# BluetoothAdapter3_0.net
KiCad netlist of a schematic drawn in Altium Designer
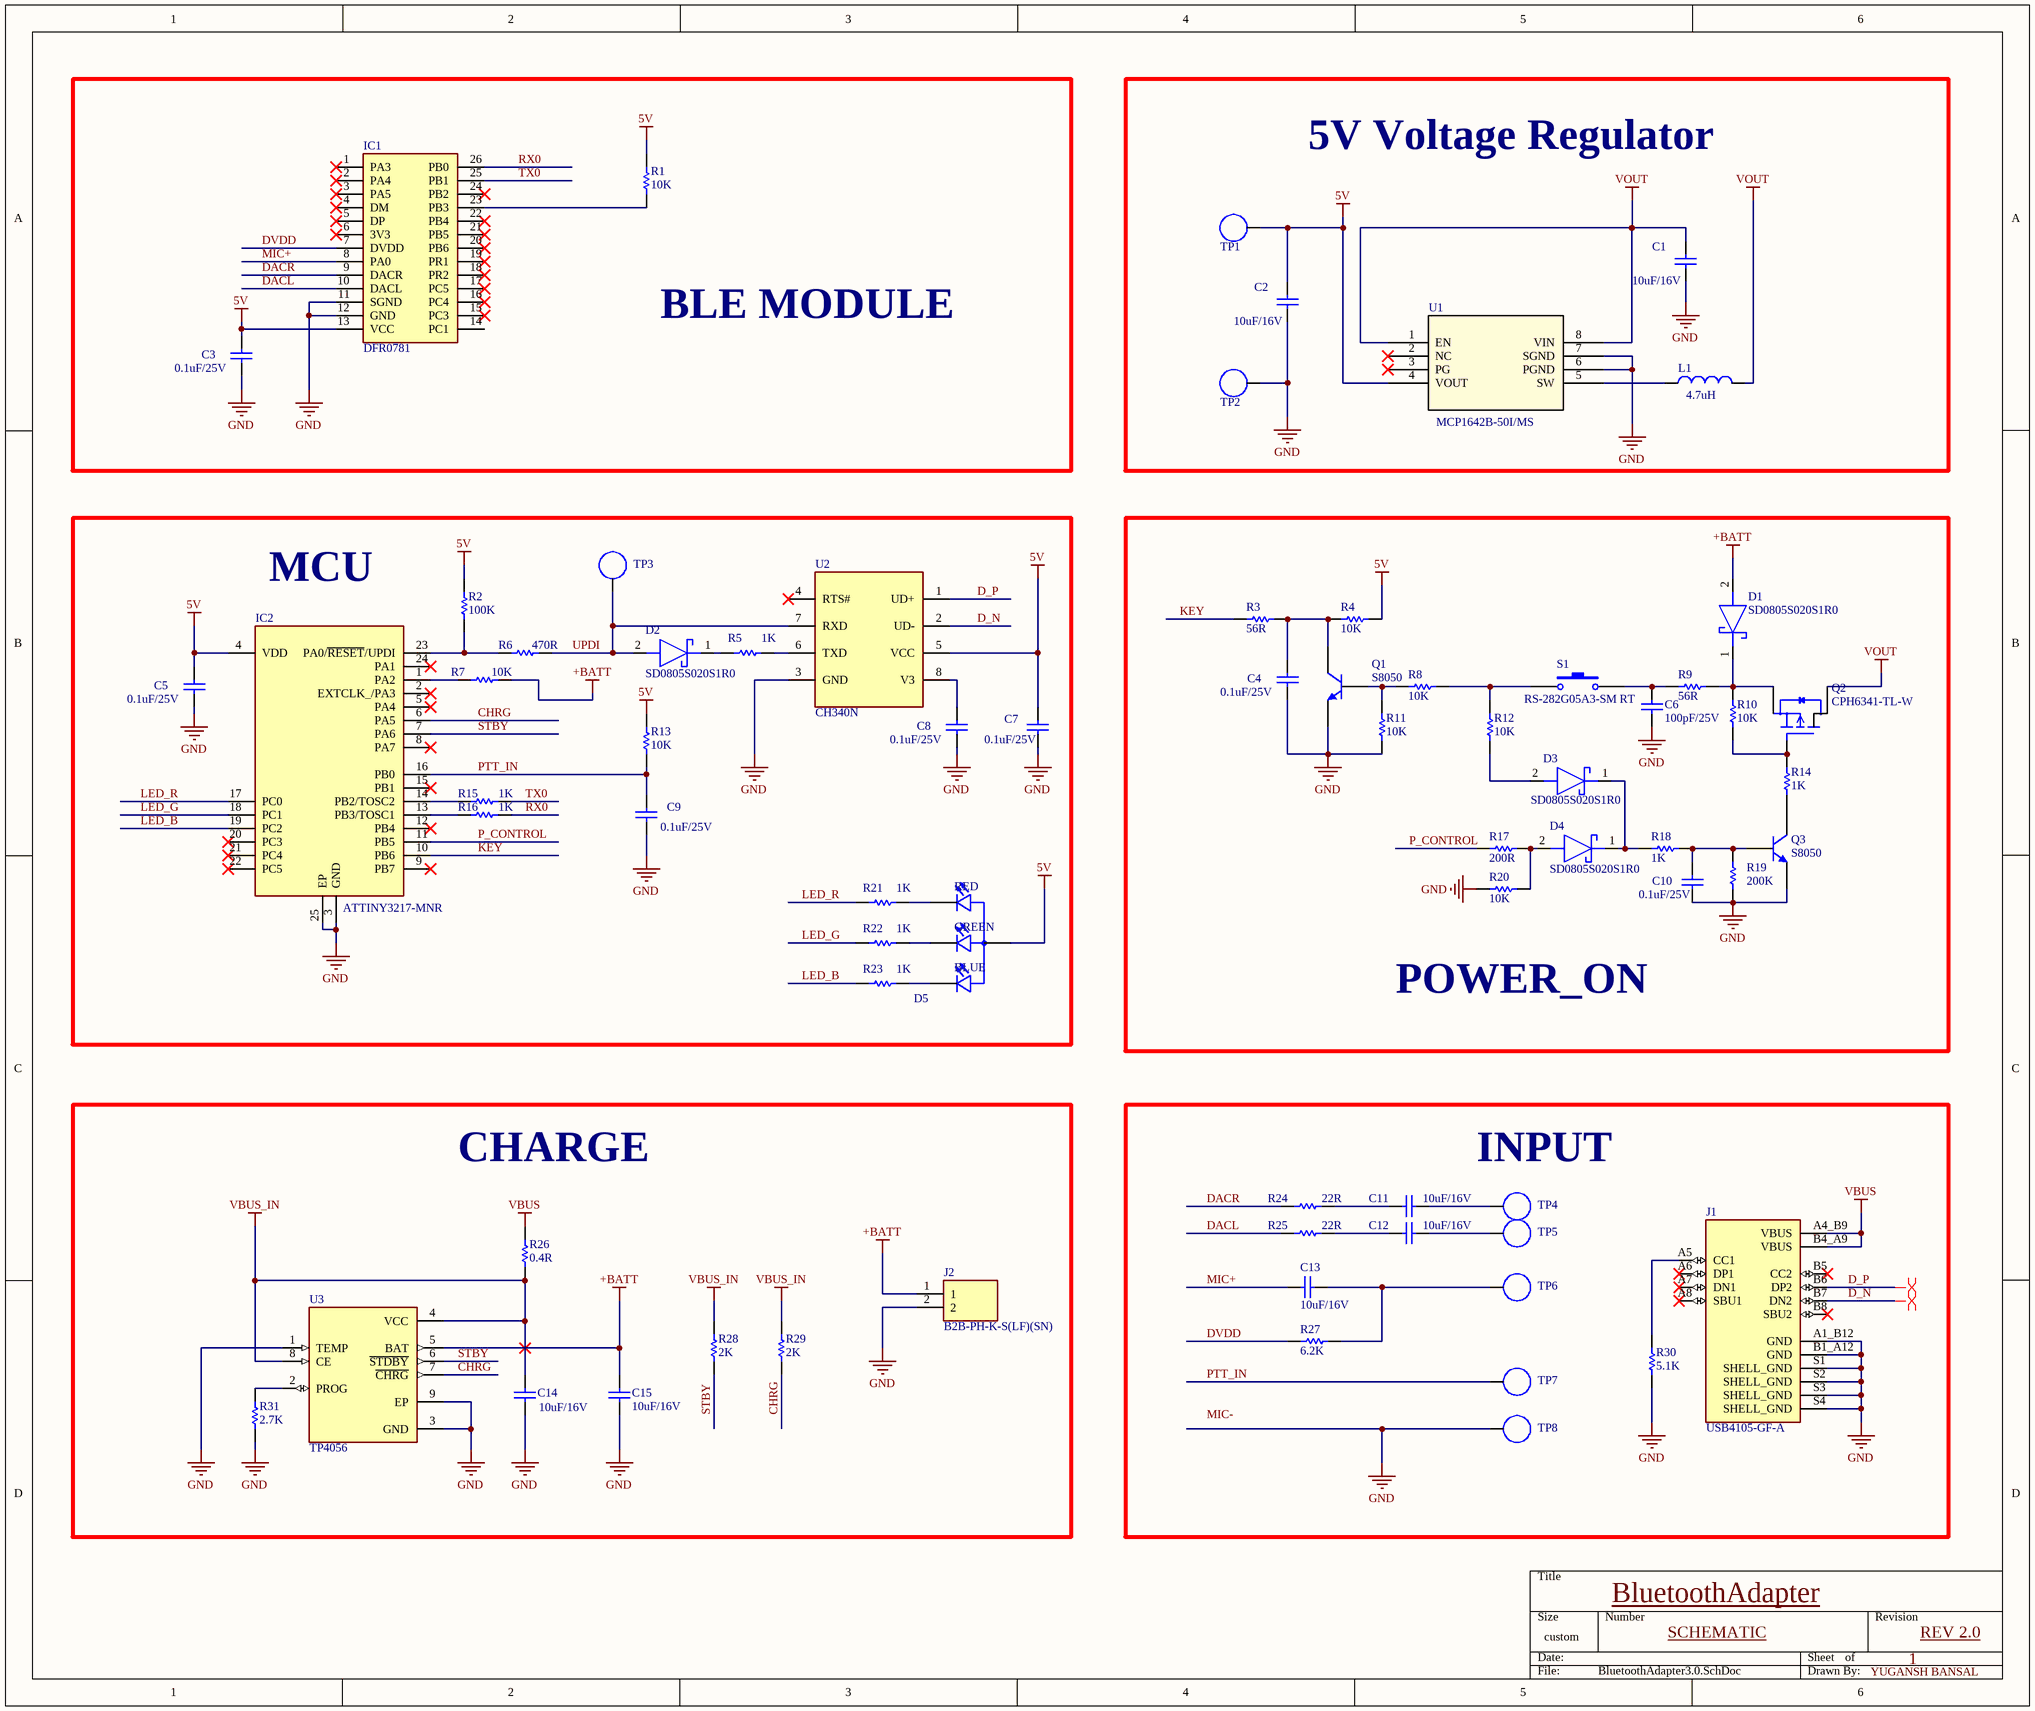
[diagram p0: BluetoothAdapter3.0.SchDoc]

(export (version "E")
  (design (tool "Eeschema 10.0.6"))
  (components
    (comp (ref "C1")
      (value "10uF/16V")
      (footprint "BluetoothAdapter:C0603S")
      (description "10 µF ±20% 16V Ceramic Capacitor X5R 0603 (1608 Metric)")
      (fields
        (field (name "MANUFACTURER") "Murata Electronics")
        (field (name "DIGI-KEY PART NUMBER") "490-10729-6-ND")
      )
      (libsource (lib "myLib") (part "Cap"))
    )
    (comp (ref "C2")
      (value "10uF/16V")
      (footprint "BluetoothAdapter:C0603S")
      (description "10 µF ±20% 16V Ceramic Capacitor X5R 0603 (1608 Metric)")
      (fields
        (field (name "MANUFACTURER") "Murata Electronics")
        (field (name "DIGI-KEY PART NUMBER") "490-10729-6-ND")
      )
      (libsource (lib "myLib") (part "Cap"))
    )
    (comp (ref "C3")
      (value "0.1uF/25V")
      (footprint "BluetoothAdapter:C0603S")
      (description "0.1 µF ±10% 25V Ceramic Capacitor X7R 0603 (1608 Metric)")
      (fields
        (field (name "MANUFACTURER") "KEMET")
        (field (name "DIGI-KEY PART NUMBER") "399-C0603C104K3RAC7867TR-ND")
      )
      (libsource (lib "myLib") (part "Cap"))
    )
    (comp (ref "C4")
      (value "0.1uF/25V")
      (footprint "BluetoothAdapter:C0603S")
      (description "0.1 µF ±10% 25V Ceramic Capacitor X7R 0603 (1608 Metric)")
      (fields
        (field (name "MANUFACTURER") "KEMET")
        (field (name "DIGI-KEY PART NUMBER") "399-C0603C104K3RAC7867TR-ND")
      )
      (libsource (lib "myLib") (part "Cap"))
    )
    (comp (ref "C5")
      (value "0.1uF/25V")
      (footprint "BluetoothAdapter:C0603S")
      (description "0.1 µF ±10% 25V Ceramic Capacitor X7R 0603 (1608 Metric)")
      (fields
        (field (name "MANUFACTURER") "KEMET")
        (field (name "DIGI-KEY PART NUMBER") "399-C0603C104K3RAC7867TR-ND")
      )
      (libsource (lib "myLib") (part "Cap"))
    )
    (comp (ref "C6")
      (value "100pF/25V")
      (footprint "BluetoothAdapter:C0603S")
      (description "0.1 µF ±10% 25V Ceramic Capacitor X7R 0603 (1608 Metric)")
      (fields
        (field (name "MANUFACTURER") "KEMET")
        (field (name "DIGI-KEY PART NUMBER") "399-C0603C101K3RACAUTODKR-ND")
      )
      (libsource (lib "myLib") (part "Cap"))
    )
    (comp (ref "C7")
      (value "0.1uF/25V")
      (footprint "BluetoothAdapter:C0603S")
      (description "0.1 µF ±10% 25V Ceramic Capacitor X7R 0603 (1608 Metric)")
      (fields
        (field (name "MANUFACTURER") "KEMET")
        (field (name "DIGI-KEY PART NUMBER") "399-C0603C104K3RAC7867TR-ND")
      )
      (libsource (lib "myLib") (part "Cap"))
    )
    (comp (ref "C8")
      (value "0.1uF/25V")
      (footprint "BluetoothAdapter:C0603S")
      (description "0.1 µF ±10% 25V Ceramic Capacitor X7R 0603 (1608 Metric)")
      (fields
        (field (name "MANUFACTURER") "KEMET")
        (field (name "DIGI-KEY PART NUMBER") "399-C0603C104K3RAC7867TR-ND")
      )
      (libsource (lib "myLib") (part "Cap"))
    )
    (comp (ref "C9")
      (value "0.1uF/25V")
      (footprint "BluetoothAdapter:C0603S")
      (description "0.1 µF ±10% 25V Ceramic Capacitor X7R 0603 (1608 Metric)")
      (fields
        (field (name "MANUFACTURER") "KEMET")
        (field (name "DIGI-KEY PART NUMBER") "399-C0603C104K3RAC7867TR-ND")
      )
      (libsource (lib "myLib") (part "Cap"))
    )
    (comp (ref "C10")
      (value "0.1uF/25V")
      (footprint "BluetoothAdapter:C0603S")
      (description "0.1 µF ±10% 25V Ceramic Capacitor X7R 0603 (1608 Metric)")
      (fields
        (field (name "MANUFACTURER") "KEMET")
        (field (name "DIGI-KEY PART NUMBER") "399-C0603C104K3RAC7867TR-ND")
      )
      (libsource (lib "myLib") (part "Cap"))
    )
    (comp (ref "C11")
      (value "10uF/16V")
      (footprint "BluetoothAdapter:C0603S")
      (description "10 µF ±20% 16V Ceramic Capacitor X5R 0603 (1608 Metric)")
      (fields
        (field (name "MANUFACTURER") "Murata Electronics")
        (field (name "DIGI-KEY PART NUMBER") "490-10729-6-ND")
      )
      (libsource (lib "myLib") (part "Cap"))
    )
    (comp (ref "C12")
      (value "10uF/16V")
      (footprint "BluetoothAdapter:C0603S")
      (description "10 µF ±20% 16V Ceramic Capacitor X5R 0603 (1608 Metric)")
      (fields
        (field (name "MANUFACTURER") "Murata Electronics")
        (field (name "DIGI-KEY PART NUMBER") "490-10729-6-ND")
      )
      (libsource (lib "myLib") (part "Cap"))
    )
    (comp (ref "C13")
      (value "10uF/16V")
      (footprint "BluetoothAdapter:C0603S")
      (description "10 µF ±20% 16V Ceramic Capacitor X5R 0603 (1608 Metric)")
      (fields
        (field (name "MANUFACTURER") "Murata Electronics")
        (field (name "DIGI-KEY PART NUMBER") "490-10729-6-ND")
      )
      (libsource (lib "myLib") (part "Cap"))
    )
    (comp (ref "C14")
      (value "10uF/16V")
      (footprint "BluetoothAdapter:C0603S")
      (description "10 µF ±20% 16V Ceramic Capacitor X5R 0603 (1608 Metric)")
      (fields
        (field (name "MANUFACTURER") "Murata Electronics")
        (field (name "DIGI-KEY PART NUMBER") "490-10729-6-ND")
      )
      (libsource (lib "myLib") (part "Cap"))
    )
    (comp (ref "C15")
      (value "10uF/16V")
      (footprint "BluetoothAdapter:C0603S")
      (description "10 µF ±20% 16V Ceramic Capacitor X5R 0603 (1608 Metric)")
      (fields
        (field (name "MANUFACTURER") "Murata Electronics")
        (field (name "DIGI-KEY PART NUMBER") "490-10729-6-ND")
      )
      (libsource (lib "myLib") (part "Cap"))
    )
    (comp (ref "D1")
      (value "SD0805S020S1R0")
      (footprint "BluetoothAdapter:DIOM1613X100N")
      (description "Diode 20 V 1A Surface Mount 0805 (2012 Metric)")
      (fields (field (name "MANUFACTURER") "AVX") (field (name "DIGI-KEY PART NUMBER") "581-SD0805S020S1R0"))
      (libsource (lib "*") (part "SD0805S020S1R0"))
    )
    (comp (ref "D2")
      (value "SD0805S020S1R0")
      (footprint "BluetoothAdapter:DIOM1613X100N")
      (description "Diode 20 V 1A Surface Mount 0805 (2012 Metric)")
      (fields (field (name "MANUFACTURER") "AVX") (field (name "DIGI-KEY PART NUMBER") "581-SD0805S020S1R0"))
      (libsource (lib "*") (part "SD0805S020S1R0"))
    )
    (comp (ref "D3")
      (value "SD0805S020S1R0")
      (footprint "BluetoothAdapter:DIOM1613X100N")
      (description "Diode 20 V 1A Surface Mount 0805 (2012 Metric)")
      (fields (field (name "MANUFACTURER") "AVX") (field (name "DIGI-KEY PART NUMBER") "581-SD0805S020S1R0"))
      (libsource (lib "*") (part "SD0805S020S1R0"))
    )
    (comp (ref "D4")
      (value "SD0805S020S1R0")
      (footprint "BluetoothAdapter:DIOM1613X100N")
      (description "Diode 20 V 1A Surface Mount 0805 (2012 Metric)")
      (fields (field (name "MANUFACTURER") "AVX") (field (name "DIGI-KEY PART NUMBER") "581-SD0805S020S1R0"))
      (libsource (lib "*") (part "SD0805S020S1R0"))
    )
    (comp (ref "D5")
      (value "LED RGB MIXED WHITE ( 1.6(L)X1.6")
      (footprint "BluetoothAdapter:LED_B38G3RGB-10D0003H2U1930")
      (description "Red, Green, Blue (RGB) LED Indication - Discrete 2V Red, 3V Green, 3V Blue 0606 (1616 Metric)")
      (fields
        (field (name "MANUFACTURER") "Harvatek Corporation")
        (field (name "DIGI-KEY PART NUMBER") "3147-B38G3RGB-10D0003H2U1930DKR-ND")
      )
      (libsource (lib "BluetoothAdapter") (part "B38G3RGB-10D0003H2U1930"))
    )
    (comp (ref "IC1")
      (value "DFR0781")
      (footprint "BluetoothAdapter:DFR0781")
      (description "Bluetooth Bluetooth v5.0 Transceiver Module Antenna Not Included Surface Mount")
      (fields (field (name "MANUFACTURER") "DFRobot") (field (name "DIGI-KEY PART NUMBER") "1738-DFR0781-ND"))
      (libsource (lib "BluetoothAdapter") (part "DFR0781"))
    )
    (comp (ref "IC2")
      (value "ATTINY3217-MNR")
      (footprint "BluetoothAdapter:QFN50P400X400X90-25N-D")
      (fields
        (field (name "MANUFACTURER") "Microchip")
        (field (name "DIGI-KEY PART NUMBER") "ATTINY3217-MNRDKR-ND")
        (field (name "Comment") "IC MCU 8BIT 32KB FLASH 24VQFN")
      )
      (libsource (lib "BluetoothAdapter") (part "ATTINY3217-MNR"))
    )
    (comp (ref "J1")
      (value "USB4105-GF-A")
      (footprint "BluetoothAdapter:GCT_USB4105-GF-A")
      (fields
        (field (name "MANUFACTURER") "GCT")
        (field (name "DIGI-KEY PART NUMBER") "2073-USB4105-GF-ADKR-ND")
        (field (name "Comment") "CONN RCP USB2.0 TYP C 24P SMD RA")
      )
      (libsource (lib "BluetoothAdapter") (part "USB4105-GF-A"))
    )
    (comp (ref "J2")
      (value "B2B-PH-K-S(LF)(SN)")
      (footprint "BluetoothAdapter:SHDR2W50P0X200_1X2_590X450X600P")
      (description "Connector Header Through Hole 2 position 0.079\" (2.00mm)")
      (fields
        (field (name "MANUFACTURER") "JST Sales America Inc.")
        (field (name "DIGI-KEY PART NUMBER") "455-1704-ND")
      )
      (libsource (lib "BluetoothAdapter") (part "B2B-PH-K-S(LF)(SN)"))
    )
    (comp (ref "L1")
      (value "4.7uH")
      (footprint "BluetoothAdapter:INDC2520X100N")
      (description "4.7 µH Shielded Multilayer Inductor 1.3 A 120mOhm 1008 (2520 Metric)")
      (fields
        (field (name "MANUFACTURER") "Abracon LLC")
        (field (name "DIGI-KEY PART NUMBER") "535-12797-6-ND")
      )
      (libsource (lib "Blueguard") (part "AIML-1008HC-4R7M-T"))
    )
    (comp (ref "Q1")
      (value "S8050")
      (footprint "BluetoothAdapter:SOT23-3D")
      (description "Bipolar (BJT) Transistor NPN 25 V 500 mA 150MHz 300 mW Surface Mount SOT-23")
      (fields (field (name "MANUFACTURER") "MDD") (field (name "DIGI-KEY PART NUMBER") "3372-S8050TR-ND"))
      (libsource (lib "BluetoothAdapter") (part "S8050"))
    )
    (comp (ref "Q2")
      (value "CPH6341-TL-W")
      (footprint "BluetoothAdapter:SOT95P285X140-6N")
      (description "P-Channel 30 V 5A (Ta) 1.6W (Ta) Surface Mount 6-CPH")
      (fields
        (field (name "MANUFACTURER") "onsemi")
        (field (name "DIGI-KEY PART NUMBER") "CPH6341-TL-WOSDKR-ND")
      )
      (libsource (lib "BluetoothAdapter") (part "CPH6341-TL-W"))
    )
    (comp (ref "Q3")
      (value "S8050")
      (footprint "BluetoothAdapter:SOT23-3D")
      (description "Bipolar (BJT) Transistor NPN 25 V 500 mA 150MHz 300 mW Surface Mount SOT-23")
      (fields (field (name "MANUFACTURER") "MDD") (field (name "DIGI-KEY PART NUMBER") "3372-S8050TR-ND"))
      (libsource (lib "BluetoothAdapter") (part "S8050"))
    )
    (comp (ref "R1")
      (value "10K")
      (footprint "BluetoothAdapter:R0603S")
      (description "10 kOhms ±1% 0.1W, 1/10W Chip Resistor 0603 (1608 Metric) Moisture Resistant Thick Film")
      (fields (field (name "MANUFACTURER") "YAGEO") (field (name "DIGI-KEY PART NUMBER") "311-10.0KHRCT-ND"))
      (libsource (lib "dif") (part "R0603"))
    )
    (comp (ref "R2")
      (value "100K")
      (footprint "BluetoothAdapter:R0603S")
      (description "100 kOhms ±1% 0.1W, 1/10W Chip Resistor 0603 (1608 Metric) Moisture Resistant Thick Film")
      (fields (field (name "MANUFACTURER") "YAGEO") (field (name "DIGI-KEY PART NUMBER") "311-100KHRDKR-ND"))
      (libsource (lib "dif") (part "R0603"))
    )
    (comp (ref "R3")
      (value "56R")
      (footprint "BluetoothAdapter:R0603S")
      (description "1 kOhms ±1% 0.1W, 1/10W Chip Resistor 0603 (1608 Metric) Moisture Resistant Thick Film")
      (fields (field (name "MANUFACTURER") "YAGEO") (field (name "DIGI-KEY PART NUMBER") "311-56.0HRDKR-ND"))
      (libsource (lib "dif") (part "R0603"))
    )
    (comp (ref "R4")
      (value "10K")
      (footprint "BluetoothAdapter:R0603S")
      (description "10 kOhms ±1% 0.1W, 1/10W Chip Resistor 0603 (1608 Metric) Moisture Resistant Thick Film")
      (fields (field (name "MANUFACTURER") "YAGEO") (field (name "DIGI-KEY PART NUMBER") "311-10.0KHRCT-ND"))
      (libsource (lib "dif") (part "R0603"))
    )
    (comp (ref "R5")
      (value "1K")
      (footprint "BluetoothAdapter:R0603S")
      (description "1 kOhms ±1% 0.1W, 1/10W Chip Resistor 0603 (1608 Metric) Moisture Resistant Thick Film")
      (fields (field (name "MANUFACTURER") "YAGEO") (field (name "DIGI-KEY PART NUMBER") "311-1.00KHRTR-ND"))
      (libsource (lib "dif") (part "R0603"))
    )
    (comp (ref "R6")
      (value "470R")
      (footprint "BluetoothAdapter:R0603S")
      (description "470 Ohms ±1% 0.1W, 1/10W Chip Resistor 0603 (1608 Metric) Moisture Resistant Thick Film")
      (fields (field (name "MANUFACTURER") "YAGEO") (field (name "DIGI-KEY PART NUMBER") "311-470HRDKR-ND"))
      (libsource (lib "dif") (part "R0603"))
    )
    (comp (ref "R7")
      (value "10K")
      (footprint "BluetoothAdapter:R0603S")
      (description "10 kOhms ±1% 0.1W, 1/10W Chip Resistor 0603 (1608 Metric) Moisture Resistant Thick Film")
      (fields (field (name "MANUFACTURER") "YAGEO") (field (name "DIGI-KEY PART NUMBER") "311-10.0KHRCT-ND"))
      (libsource (lib "dif") (part "R0603"))
    )
    (comp (ref "R8")
      (value "10K")
      (footprint "BluetoothAdapter:R0603S")
      (description "10 kOhms ±1% 0.1W, 1/10W Chip Resistor 0603 (1608 Metric) Moisture Resistant Thick Film")
      (fields (field (name "MANUFACTURER") "YAGEO") (field (name "DIGI-KEY PART NUMBER") "311-10.0KHRCT-ND"))
      (libsource (lib "dif") (part "R0603"))
    )
    (comp (ref "R9")
      (value "56R")
      (footprint "BluetoothAdapter:R0603S")
      (description "1 kOhms ±1% 0.1W, 1/10W Chip Resistor 0603 (1608 Metric) Moisture Resistant Thick Film")
      (fields (field (name "MANUFACTURER") "YAGEO") (field (name "DIGI-KEY PART NUMBER") "311-56.0HRDKR-ND"))
      (libsource (lib "dif") (part "R0603"))
    )
    (comp (ref "R10")
      (value "10K")
      (footprint "BluetoothAdapter:R0603S")
      (description "10 kOhms ±1% 0.1W, 1/10W Chip Resistor 0603 (1608 Metric) Moisture Resistant Thick Film")
      (fields (field (name "MANUFACTURER") "YAGEO") (field (name "DIGI-KEY PART NUMBER") "311-10.0KHRCT-ND"))
      (libsource (lib "dif") (part "R0603"))
    )
    (comp (ref "R11")
      (value "10K")
      (footprint "BluetoothAdapter:R0603S")
      (description "10 kOhms ±1% 0.1W, 1/10W Chip Resistor 0603 (1608 Metric) Moisture Resistant Thick Film")
      (fields (field (name "MANUFACTURER") "YAGEO") (field (name "DIGI-KEY PART NUMBER") "311-10.0KHRCT-ND"))
      (libsource (lib "dif") (part "R0603"))
    )
    (comp (ref "R12")
      (value "10K")
      (footprint "BluetoothAdapter:R0603S")
      (description "10 kOhms ±1% 0.1W, 1/10W Chip Resistor 0603 (1608 Metric) Moisture Resistant Thick Film")
      (fields (field (name "MANUFACTURER") "YAGEO") (field (name "DIGI-KEY PART NUMBER") "311-10.0KHRCT-ND"))
      (libsource (lib "dif") (part "R0603"))
    )
    (comp (ref "R13")
      (value "10K")
      (footprint "BluetoothAdapter:R0603S")
      (description "10 kOhms ±1% 0.1W, 1/10W Chip Resistor 0603 (1608 Metric) Moisture Resistant Thick Film")
      (fields (field (name "MANUFACTURER") "YAGEO") (field (name "DIGI-KEY PART NUMBER") "311-10.0KHRCT-ND"))
      (libsource (lib "dif") (part "R0603"))
    )
    (comp (ref "R14")
      (value "1K")
      (footprint "BluetoothAdapter:R0603S")
      (description "1 kOhms ±1% 0.1W, 1/10W Chip Resistor 0603 (1608 Metric) Moisture Resistant Thick Film")
      (fields (field (name "MANUFACTURER") "YAGEO") (field (name "DIGI-KEY PART NUMBER") "311-1.00KHRTR-ND"))
      (libsource (lib "dif") (part "R0603"))
    )
    (comp (ref "R15")
      (value "1K")
      (footprint "BluetoothAdapter:R0603S")
      (description "1 kOhms ±1% 0.1W, 1/10W Chip Resistor 0603 (1608 Metric) Moisture Resistant Thick Film")
      (fields (field (name "MANUFACTURER") "YAGEO") (field (name "DIGI-KEY PART NUMBER") "311-1.00KHRTR-ND"))
      (libsource (lib "dif") (part "R0603"))
    )
    (comp (ref "R16")
      (value "1K")
      (footprint "BluetoothAdapter:R0603S")
      (description "1 kOhms ±1% 0.1W, 1/10W Chip Resistor 0603 (1608 Metric) Moisture Resistant Thick Film")
      (fields (field (name "MANUFACTURER") "YAGEO") (field (name "DIGI-KEY PART NUMBER") "311-1.00KHRTR-ND"))
      (libsource (lib "dif") (part "R0603"))
    )
    (comp (ref "R17")
      (value "200R")
      (footprint "BluetoothAdapter:R0603S")
      (description "10 kOhms ±1% 0.1W, 1/10W Chip Resistor 0603 (1608 Metric) Moisture Resistant Thick Film")
      (fields (field (name "MANUFACTURER") "YAGEO") (field (name "DIGI-KEY PART NUMBER") "311-200HRDKR-ND"))
      (libsource (lib "dif") (part "R0603"))
    )
    (comp (ref "R18")
      (value "1K")
      (footprint "BluetoothAdapter:R0603S")
      (description "1 kOhms ±1% 0.1W, 1/10W Chip Resistor 0603 (1608 Metric) Moisture Resistant Thick Film")
      (fields (field (name "MANUFACTURER") "YAGEO") (field (name "DIGI-KEY PART NUMBER") "311-1.00KHRTR-ND"))
      (libsource (lib "dif") (part "R0603"))
    )
    (comp (ref "R19")
      (value "200K")
      (footprint "BluetoothAdapter:R0603S")
      (description "100 kOhms ±1% 0.1W, 1/10W Chip Resistor 0603 (1608 Metric) Moisture Resistant Thick Film")
      (fields
        (field (name "MANUFACTURER") "YAGEO")
        (field (name "DIGI-KEY PART NUMBER") "13-RC0603FR-10200KLDKR-ND")
      )
      (libsource (lib "dif") (part "R0603"))
    )
    (comp (ref "R20")
      (value "10K")
      (footprint "BluetoothAdapter:R0603S")
      (description "10 kOhms ±1% 0.1W, 1/10W Chip Resistor 0603 (1608 Metric) Moisture Resistant Thick Film")
      (fields (field (name "MANUFACTURER") "YAGEO") (field (name "DIGI-KEY PART NUMBER") "311-10.0KHRCT-ND"))
      (libsource (lib "dif") (part "R0603"))
    )
    (comp (ref "R21")
      (value "1K")
      (footprint "BluetoothAdapter:R0603S")
      (description "1 kOhms ±1% 0.1W, 1/10W Chip Resistor 0603 (1608 Metric) Moisture Resistant Thick Film")
      (fields (field (name "MANUFACTURER") "YAGEO") (field (name "DIGI-KEY PART NUMBER") "311-1.00KHRTR-ND"))
      (libsource (lib "dif") (part "R0603"))
    )
    (comp (ref "R22")
      (value "1K")
      (footprint "BluetoothAdapter:R0603S")
      (description "1 kOhms ±1% 0.1W, 1/10W Chip Resistor 0603 (1608 Metric) Moisture Resistant Thick Film")
      (fields (field (name "MANUFACTURER") "YAGEO") (field (name "DIGI-KEY PART NUMBER") "311-1.00KHRTR-ND"))
      (libsource (lib "dif") (part "R0603"))
    )
    (comp (ref "R23")
      (value "1K")
      (footprint "BluetoothAdapter:R0603S")
      (description "1 kOhms ±1% 0.1W, 1/10W Chip Resistor 0603 (1608 Metric) Moisture Resistant Thick Film")
      (fields (field (name "MANUFACTURER") "YAGEO") (field (name "DIGI-KEY PART NUMBER") "311-1.00KHRTR-ND"))
      (libsource (lib "dif") (part "R0603"))
    )
    (comp (ref "R24")
      (value "22R")
      (footprint "BluetoothAdapter:R0603S")
      (description "22 Ohms ±5% 0.1W, 1/10W Chip Resistor 0603 (1608 Metric) Moisture Resistant Thick Film")
      (fields (field (name "MANUFACTURER") "YAGEO") (field (name "DIGI-KEY PART NUMBER") "311-22GRDKR-ND"))
      (libsource (lib "dif") (part "R0603"))
    )
    (comp (ref "R25")
      (value "22R")
      (footprint "BluetoothAdapter:R0603S")
      (description "22 Ohms ±5% 0.1W, 1/10W Chip Resistor 0603 (1608 Metric) Moisture Resistant Thick Film")
      (fields (field (name "MANUFACTURER") "YAGEO") (field (name "DIGI-KEY PART NUMBER") "311-22GRDKR-ND"))
      (libsource (lib "dif") (part "R0603"))
    )
    (comp (ref "R26")
      (value "0.4R")
      (footprint "BluetoothAdapter:R1206S")
      (fields
        (field (name "MANUFACTURER") "YAGEO")
        (field (name "DIGI-KEY PART NUMBER") "311-.4LWDKR-ND")
        (field (name "Comment") "RES 0.4 OHM 1% 1/4W 1206")
      )
      (libsource (lib "dif") (part "R0603"))
    )
    (comp (ref "R27")
      (value "6.2K")
      (footprint "BluetoothAdapter:R0603S")
      (description "6.2 kOhms ±1% 0.1W, 1/10W Chip Resistor 0603 (1608 Metric) Moisture Resistant Thick Film")
      (fields (field (name "MANUFACTURER") "YAGEO") (field (name "DIGI-KEY PART NUMBER") "311-6.20KHRDKR-ND"))
      (libsource (lib "dif") (part "R0603"))
    )
    (comp (ref "R28")
      (value "2K")
      (footprint "BluetoothAdapter:R0603S")
      (description "2 kOhms ±1% 0.1W, 1/10W Chip Resistor 0603 (1608 Metric) Moisture Resistant Thick Film")
      (fields (field (name "MANUFACTURER") "YAGEO") (field (name "DIGI-KEY PART NUMBER") "311-2.00KHRDKR-ND"))
      (libsource (lib "dif") (part "R0603"))
    )
    (comp (ref "R29")
      (value "2K")
      (footprint "BluetoothAdapter:R0603S")
      (description "2 kOhms ±1% 0.1W, 1/10W Chip Resistor 0603 (1608 Metric) Moisture Resistant Thick Film")
      (fields (field (name "MANUFACTURER") "YAGEO") (field (name "DIGI-KEY PART NUMBER") "311-2.00KHRDKR-ND"))
      (libsource (lib "dif") (part "R0603"))
    )
    (comp (ref "R30")
      (value "5.1K")
      (footprint "BluetoothAdapter:R0603S")
      (description "5.1kOhms ±1% 0.1W, 1/10W Chip Resistor 0603 (1608 Metric) Moisture Resistant Thick Film")
      (fields (field (name "MANUFACTURER") "YAGEO") (field (name "DIGI-KEY PART NUMBER") "311-5.10KHRDKR-ND"))
      (libsource (lib "dif") (part "R0603"))
    )
    (comp (ref "R31")
      (value "2.7K")
      (footprint "BluetoothAdapter:R0603S")
      (description "2.7 kOhms ±1% 0.1W, 1/10W Chip Resistor 0603 (1608 Metric) Moisture Resistant Thick Film")
      (fields (field (name "MANUFACTURER") "YAGEO") (field (name "DIGI-KEY PART NUMBER") "311-2.70KHRDKR-ND"))
      (libsource (lib "dif") (part "R0603"))
    )
    (comp (ref "S1")
      (value "RS-282G05A3-SM RT")
      (footprint "BluetoothAdapter:RS282G05A3SMRT")
      (description "Tactile Switch SPST-NO Top Actuated Surface Mount")
      (fields
        (field (name "MANUFACTURER") "C & K COMPONENTS")
        (field (name "DIGI-KEY PART NUMBER") "CKN10384DKR-ND")
      )
      (libsource (lib "BluetoothAdapter") (part "RS282G05A3SMRT"))
    )
    (comp (ref "TP1")
      (value "TP")
      (footprint "BluetoothAdapter:TP")
      (libsource (lib "BluetoothAdapter") (part "TP"))
    )
    (comp (ref "TP2")
      (value "TP")
      (footprint "BluetoothAdapter:TP")
      (libsource (lib "BluetoothAdapter") (part "TP"))
    )
    (comp (ref "TP3")
      (value "TP")
      (footprint "BluetoothAdapter:TP")
      (libsource (lib "BluetoothAdapter") (part "TP"))
    )
    (comp (ref "TP4")
      (value "TP")
      (footprint "BluetoothAdapter:TP")
      (libsource (lib "BluetoothAdapter") (part "TP"))
    )
    (comp (ref "TP5")
      (value "TP")
      (footprint "BluetoothAdapter:TP")
      (libsource (lib "BluetoothAdapter") (part "TP"))
    )
    (comp (ref "TP6")
      (value "TP")
      (footprint "BluetoothAdapter:TP")
      (libsource (lib "BluetoothAdapter") (part "TP"))
    )
    (comp (ref "TP7")
      (value "TP")
      (footprint "BluetoothAdapter:TP")
      (libsource (lib "BluetoothAdapter") (part "TP"))
    )
    (comp (ref "TP8")
      (value "TP")
      (footprint "BluetoothAdapter:TP")
      (libsource (lib "BluetoothAdapter") (part "TP"))
    )
    (comp (ref "U1")
      (value "MCP1642B-50I/MS")
      (footprint "BluetoothAdapter:MCP1642B-50I/MS")
      (fields
        (field (name "MANUFACTURER") "Microchip Technology")
        (field (name "DIGI-KEY PART NUMBER") "MCP1642B-50I/MS-ND")
        (field (name "Comment") "IC REG BOOST 5V 800MA 8MSOP")
      )
      (libsource (lib "Blueguard") (part "MCP1642B-50I/MS"))
    )
    (comp (ref "U2")
      (value "CH340N")
      (footprint "BluetoothAdapter:SOIC127P602X173-8N")
      (description "IC USB TO UART BRIDGE SOP-8")
      (fields
        (field (name "MANUFACTURER") "WCH(Jiangsu Qin Heng)")
        (field (name "DIGI-KEY PART NUMBER") "C506813")
      )
      (libsource (lib "BluetoothAdapter") (part "CH340N"))
    )
    (comp (ref "U3")
      (value "TP4056")
      (footprint "BluetoothAdapter:SOP127P600X175-9N")
      (description "Complete single cell Li-Ion battery with a constant current / constant voltage linear charger")
      (fields
        (field (name "MANUFACTURER") "TPOWER semiconductor Co.,LTD.")
        (field (name "DIGI-KEY PART NUMBER") "C382139")
      )
      (libsource (lib "BluetoothAdapter") (part "TP4056"))
    )
  )
  (nets
    (net (code "1") (name "+BATT") (class "Default")
      (node (ref "C15") (pin "2") (pinfunction "2_2") (pintype "passive"))
      (node (ref "D1") (pin "2") (pinfunction "A_2") (pintype "passive"))
      (node (ref "J2") (pin "1") (pinfunction "1_1") (pintype "passive"))
      (node (ref "R7") (pin "2") (pinfunction "2_2") (pintype "passive"))
      (node (ref "U3") (pin "5") (pinfunction "BAT_5") (pintype "output"))
    )
    (net (code "2") (name "/CHRG") (class "Default")
      (node (ref "IC2") (pin "6") (pinfunction "PA5_6") (pintype "passive"))
      (node (ref "R29") (pin "2") (pinfunction "2_2") (pintype "passive"))
      (node (ref "U3") (pin "7") (pinfunction "~{CHRG}_7") (pintype "output"))
    )
    (net (code "3") (name "/DACL") (class "Default")
      (node (ref "IC1") (pin "10") (pinfunction "DACL_10") (pintype "passive"))
      (node (ref "R25") (pin "1") (pinfunction "1_1") (pintype "passive"))
    )
    (net (code "4") (name "/DACR") (class "Default")
      (node (ref "IC1") (pin "9") (pinfunction "DACR_9") (pintype "passive"))
      (node (ref "R24") (pin "1") (pinfunction "1_1") (pintype "passive"))
    )
    (net (code "5") (name "/DVDD") (class "Default")
      (node (ref "IC1") (pin "7") (pinfunction "DVDD_7") (pintype "passive"))
      (node (ref "R27") (pin "1") (pinfunction "1_1") (pintype "passive"))
    )
    (net (code "6") (name "/D_N") (class "Default")
      (node (ref "J1") (pin "B7") (pinfunction "DN2_B7") (pintype "bidirectional"))
      (node (ref "U2") (pin "2") (pinfunction "UD-_2") (pintype "passive"))
    )
    (net (code "7") (name "/D_P") (class "Default")
      (node (ref "J1") (pin "B6") (pinfunction "DP2_B6") (pintype "bidirectional"))
      (node (ref "U2") (pin "1") (pinfunction "UD+_1") (pintype "passive"))
    )
    (net (code "8") (name "/KEY") (class "Default")
      (node (ref "IC2") (pin "10") (pinfunction "PB6_10") (pintype "passive"))
      (node (ref "R3") (pin "1") (pinfunction "1_1") (pintype "passive"))
    )
    (net (code "9") (name "/LED_B") (class "Default")
      (node (ref "IC2") (pin "19") (pinfunction "PC2_19") (pintype "passive"))
      (node (ref "R23") (pin "1") (pinfunction "1_1") (pintype "passive"))
    )
    (net (code "10") (name "/LED_G") (class "Default")
      (node (ref "IC2") (pin "18") (pinfunction "PC1_18") (pintype "passive"))
      (node (ref "R22") (pin "1") (pinfunction "1_1") (pintype "passive"))
    )
    (net (code "11") (name "/LED_R") (class "Default")
      (node (ref "IC2") (pin "17") (pinfunction "PC0_17") (pintype "passive"))
      (node (ref "R21") (pin "1") (pinfunction "1_1") (pintype "passive"))
    )
    (net (code "12") (name "/MIC+") (class "Default")
      (node (ref "C13") (pin "2") (pinfunction "2_2") (pintype "passive"))
      (node (ref "IC1") (pin "8") (pinfunction "PA0_8") (pintype "passive"))
    )
    (net (code "14") (name "/PTT_IN") (class "Default")
      (node (ref "C9") (pin "1") (pinfunction "1_1") (pintype "passive"))
      (node (ref "IC2") (pin "16") (pinfunction "PB0_16") (pintype "passive"))
      (node (ref "R13") (pin "2") (pinfunction "2_2") (pintype "passive"))
      (node (ref "TP7") (pin "1") (pinfunction "1_1") (pintype "passive"))
    )
    (net (code "15") (name "/P_CONTROL") (class "Default")
      (node (ref "IC2") (pin "11") (pinfunction "PB5_11") (pintype "passive"))
      (node (ref "R17") (pin "1") (pinfunction "1_1") (pintype "passive"))
    )
    (net (code "16") (name "/RX0") (class "Default")
      (node (ref "IC1") (pin "26") (pinfunction "PB0_26") (pintype "passive"))
      (node (ref "R16") (pin "2") (pinfunction "2_2") (pintype "passive"))
    )
    (net (code "17") (name "/STBY") (class "Default")
      (node (ref "IC2") (pin "7") (pinfunction "PA6_7") (pintype "passive"))
      (node (ref "R28") (pin "2") (pinfunction "2_2") (pintype "passive"))
      (node (ref "U3") (pin "6") (pinfunction "~{STDBY}_6") (pintype "output"))
    )
    (net (code "18") (name "/TX0") (class "Default")
      (node (ref "IC1") (pin "25") (pinfunction "PB1_25") (pintype "passive"))
      (node (ref "R15") (pin "2") (pinfunction "2_2") (pintype "passive"))
    )
    (net (code "19") (name "/UPDI") (class "Default")
      (node (ref "D2") (pin "2") (pinfunction "A_2") (pintype "passive"))
      (node (ref "R6") (pin "1") (pinfunction "1_1") (pintype "passive"))
      (node (ref "TP3") (pin "1") (pinfunction "1_1") (pintype "passive"))
      (node (ref "U2") (pin "7") (pinfunction "RXD_7") (pintype "power_in"))
    )
    (net (code "20") (name "5V") (class "Default")
      (node (ref "C2") (pin "2") (pinfunction "2_2") (pintype "passive"))
      (node (ref "C3") (pin "1") (pinfunction "1_1") (pintype "passive"))
      (node (ref "C5") (pin "1") (pinfunction "1_1") (pintype "passive"))
      (node (ref "C7") (pin "1") (pinfunction "1_1") (pintype "passive"))
      (node (ref "D5") (pin "3") (pinfunction "A_3") (pintype "passive"))
      (node (ref "IC1") (pin "13") (pinfunction "VCC_13") (pintype "passive"))
      (node (ref "IC2") (pin "4") (pinfunction "VDD_4") (pintype "passive"))
      (node (ref "R1") (pin "2") (pinfunction "2_2") (pintype "passive"))
      (node (ref "R13") (pin "1") (pinfunction "1_1") (pintype "passive"))
      (node (ref "R2") (pin "1") (pinfunction "1_1") (pintype "passive"))
      (node (ref "R4") (pin "1") (pinfunction "1_1") (pintype "passive"))
      (node (ref "TP1") (pin "1") (pinfunction "1_1") (pintype "passive"))
      (node (ref "U1") (pin "4") (pinfunction "VOUT_4") (pintype "passive"))
      (node (ref "U2") (pin "5") (pinfunction "VCC_5") (pintype "passive"))
    )
    (net (code "21") (name "GND") (class "Default")
      (node (ref "C1") (pin "1") (pinfunction "1_1") (pintype "passive"))
      (node (ref "C10") (pin "2") (pinfunction "2_2") (pintype "passive"))
      (node (ref "C14") (pin "1") (pinfunction "1_1") (pintype "passive"))
      (node (ref "C15") (pin "1") (pinfunction "1_1") (pintype "passive"))
      (node (ref "C2") (pin "1") (pinfunction "1_1") (pintype "passive"))
      (node (ref "C3") (pin "2") (pinfunction "2_2") (pintype "passive"))
      (node (ref "C4") (pin "2") (pinfunction "2_2") (pintype "passive"))
      (node (ref "C5") (pin "2") (pinfunction "2_2") (pintype "passive"))
      (node (ref "C6") (pin "1") (pinfunction "1_1") (pintype "passive"))
      (node (ref "C7") (pin "2") (pinfunction "2_2") (pintype "passive"))
      (node (ref "C8") (pin "2") (pinfunction "2_2") (pintype "passive"))
      (node (ref "C9") (pin "2") (pinfunction "2_2") (pintype "passive"))
      (node (ref "IC1") (pin "11") (pinfunction "SGND_11") (pintype "passive"))
      (node (ref "IC1") (pin "12") (pinfunction "GND_12") (pintype "passive"))
      (node (ref "IC2") (pin "25") (pinfunction "EP_25") (pintype "passive"))
      (node (ref "IC2") (pin "3") (pinfunction "GND_3") (pintype "passive"))
      (node (ref "J1") (pin "A1_B12") (pinfunction "GND_A1_B12") (pintype "power_in"))
      (node (ref "J1") (pin "B1_A12") (pinfunction "GND_B1_A12") (pintype "power_in"))
      (node (ref "J1") (pin "S1") (pinfunction "SHELL_GND_S1") (pintype "power_in"))
      (node (ref "J1") (pin "S2") (pinfunction "SHELL_GND_S2") (pintype "power_in"))
      (node (ref "J1") (pin "S3") (pinfunction "SHELL_GND_S3") (pintype "power_in"))
      (node (ref "J1") (pin "S4") (pinfunction "SHELL_GND_S4") (pintype "power_in"))
      (node (ref "J2") (pin "2") (pinfunction "2_2") (pintype "passive"))
      (node (ref "Q1") (pin "3") (pinfunction "E_3") (pintype "passive"))
      (node (ref "Q3") (pin "3") (pinfunction "E_3") (pintype "passive"))
      (node (ref "R11") (pin "2") (pinfunction "2_2") (pintype "passive"))
      (node (ref "R19") (pin "1") (pinfunction "1_1") (pintype "passive"))
      (node (ref "R20") (pin "1") (pinfunction "1_1") (pintype "passive"))
      (node (ref "R30") (pin "2") (pinfunction "2_2") (pintype "passive"))
      (node (ref "R31") (pin "2") (pinfunction "2_2") (pintype "passive"))
      (node (ref "TP2") (pin "1") (pinfunction "1_1") (pintype "passive"))
      (node (ref "TP8") (pin "1") (pinfunction "1_1") (pintype "passive"))
      (node (ref "U1") (pin "6") (pinfunction "PGND_6") (pintype "passive"))
      (node (ref "U1") (pin "7") (pinfunction "SGND_7") (pintype "passive"))
      (node (ref "U2") (pin "3") (pinfunction "GND_3") (pintype "passive"))
      (node (ref "U3") (pin "1") (pinfunction "TEMP_1") (pintype "input"))
      (node (ref "U3") (pin "3") (pinfunction "GND_3") (pintype "power_in"))
      (node (ref "U3") (pin "9") (pinfunction "EP_9") (pintype "passive"))
    )
    (net (code "22") (name "Net-(C6-Pad2)") (class "Default")
      (node (ref "C6") (pin "2") (pinfunction "2_2") (pintype "passive"))
      (node (ref "R9") (pin "1") (pinfunction "1_1") (pintype "passive"))
      (node (ref "S1") (pin "2") (pinfunction "2_2") (pintype "passive"))
    )
    (net (code "23") (name "Net-(C11-Pad1)") (class "Default")
      (node (ref "C11") (pin "1") (pinfunction "1_1") (pintype "passive"))
      (node (ref "TP4") (pin "1") (pinfunction "1_1") (pintype "passive"))
    )
    (net (code "24") (name "Net-(C11-Pad2)") (class "Default")
      (node (ref "C11") (pin "2") (pinfunction "2_2") (pintype "passive"))
      (node (ref "R24") (pin "2") (pinfunction "2_2") (pintype "passive"))
    )
    (net (code "25") (name "Net-(C12-Pad1)") (class "Default")
      (node (ref "C12") (pin "1") (pinfunction "1_1") (pintype "passive"))
      (node (ref "TP5") (pin "1") (pinfunction "1_1") (pintype "passive"))
    )
    (net (code "26") (name "Net-(C12-Pad2)") (class "Default")
      (node (ref "C12") (pin "2") (pinfunction "2_2") (pintype "passive"))
      (node (ref "R25") (pin "2") (pinfunction "2_2") (pintype "passive"))
    )
    (net (code "27") (name "Net-(C13-Pad1)") (class "Default")
      (node (ref "C13") (pin "1") (pinfunction "1_1") (pintype "passive"))
      (node (ref "R27") (pin "2") (pinfunction "2_2") (pintype "passive"))
      (node (ref "TP6") (pin "1") (pinfunction "1_1") (pintype "passive"))
    )
    (net (code "28") (name "Net-(D1-K)") (class "Default")
      (node (ref "D1") (pin "1") (pinfunction "K_1") (pintype "passive"))
      (node (ref "Q2") (pin "4") (pinfunction "S_4") (pintype "passive"))
      (node (ref "R10") (pin "1") (pinfunction "1_1") (pintype "passive"))
      (node (ref "R9") (pin "2") (pinfunction "2_2") (pintype "passive"))
    )
    (net (code "29") (name "Net-(D2-K)") (class "Default")
      (node (ref "D2") (pin "1") (pinfunction "K_1") (pintype "passive"))
      (node (ref "R5") (pin "1") (pinfunction "1_1") (pintype "passive"))
    )
    (net (code "30") (name "Net-(D3-A)") (class "Default")
      (node (ref "D3") (pin "2") (pinfunction "A_2") (pintype "passive"))
      (node (ref "R12") (pin "2") (pinfunction "2_2") (pintype "passive"))
    )
    (net (code "31") (name "Net-(D3-K)") (class "Default")
      (node (ref "D3") (pin "1") (pinfunction "K_1") (pintype "passive"))
      (node (ref "D4") (pin "1") (pinfunction "K_1") (pintype "passive"))
      (node (ref "R18") (pin "2") (pinfunction "2_2") (pintype "passive"))
    )
    (net (code "32") (name "Net-(D4-A)") (class "Default")
      (node (ref "D4") (pin "2") (pinfunction "A_2") (pintype "passive"))
      (node (ref "R17") (pin "2") (pinfunction "2_2") (pintype "passive"))
      (node (ref "R20") (pin "2") (pinfunction "2_2") (pintype "passive"))
    )
    (net (code "33") (name "Net-(D5-B_C)") (class "Default")
      (node (ref "D5") (pin "2") (pinfunction "B_C_2") (pintype "passive"))
      (node (ref "R23") (pin "2") (pinfunction "2_2") (pintype "passive"))
    )
    (net (code "34") (name "Net-(D5-G_C)") (class "Default")
      (node (ref "D5") (pin "1") (pinfunction "G_C_1") (pintype "passive"))
      (node (ref "R22") (pin "2") (pinfunction "2_2") (pintype "passive"))
    )
    (net (code "35") (name "Net-(D5-R_C)") (class "Default")
      (node (ref "D5") (pin "4") (pinfunction "R_C_4") (pintype "passive"))
      (node (ref "R21") (pin "2") (pinfunction "2_2") (pintype "passive"))
    )
    (net (code "36") (name "Net-(IC1-PB3)") (class "Default")
      (node (ref "IC1") (pin "23") (pinfunction "PB3_23") (pintype "passive"))
      (node (ref "R1") (pin "1") (pinfunction "1_1") (pintype "passive"))
    )
    (net (code "37") (name "Net-(IC2-PA0{slash}~{RESET}{slash}UPDI)") (class "Default")
      (node (ref "IC2") (pin "23") (pinfunction "PA0/~{RESET}/UPDI_23") (pintype "passive"))
      (node (ref "R2") (pin "2") (pinfunction "2_2") (pintype "passive"))
      (node (ref "R6") (pin "2") (pinfunction "2_2") (pintype "passive"))
    )
    (net (code "38") (name "Net-(IC2-PA2)") (class "Default")
      (node (ref "IC2") (pin "1") (pinfunction "PA2_1") (pintype "passive"))
      (node (ref "R7") (pin "1") (pinfunction "1_1") (pintype "passive"))
    )
    (net (code "39") (name "Net-(IC2-PB2{slash}TOSC2)") (class "Default")
      (node (ref "IC2") (pin "14") (pinfunction "PB2/TOSC2_14") (pintype "passive"))
      (node (ref "R15") (pin "1") (pinfunction "1_1") (pintype "passive"))
    )
    (net (code "40") (name "Net-(IC2-PB3{slash}TOSC1)") (class "Default")
      (node (ref "IC2") (pin "13") (pinfunction "PB3/TOSC1_13") (pintype "passive"))
      (node (ref "R16") (pin "1") (pinfunction "1_1") (pintype "passive"))
    )
    (net (code "41") (name "Net-(J1-CC1)") (class "Default")
      (node (ref "J1") (pin "A5") (pinfunction "CC1_A5") (pintype "bidirectional"))
      (node (ref "R30") (pin "1") (pinfunction "1_1") (pintype "passive"))
    )
    (net (code "42") (name "Net-(Q1-B)") (class "Default")
      (node (ref "Q1") (pin "1") (pinfunction "B_1") (pintype "passive"))
      (node (ref "R11") (pin "1") (pinfunction "1_1") (pintype "passive"))
      (node (ref "R8") (pin "2") (pinfunction "2_2") (pintype "passive"))
    )
    (net (code "43") (name "Net-(Q1-C)") (class "Default")
      (node (ref "C4") (pin "1") (pinfunction "1_1") (pintype "passive"))
      (node (ref "Q1") (pin "2") (pinfunction "C_2") (pintype "passive"))
      (node (ref "R3") (pin "2") (pinfunction "2_2") (pintype "passive"))
      (node (ref "R4") (pin "2") (pinfunction "2_2") (pintype "passive"))
    )
    (net (code "44") (name "Net-(Q2-G)") (class "Default")
      (node (ref "Q2") (pin "3") (pinfunction "G_3") (pintype "passive"))
      (node (ref "R10") (pin "2") (pinfunction "2_2") (pintype "passive"))
      (node (ref "R14") (pin "1") (pinfunction "1_1") (pintype "passive"))
    )
    (net (code "45") (name "Net-(Q3-B)") (class "Default")
      (node (ref "C10") (pin "1") (pinfunction "1_1") (pintype "passive"))
      (node (ref "Q3") (pin "1") (pinfunction "B_1") (pintype "passive"))
      (node (ref "R18") (pin "1") (pinfunction "1_1") (pintype "passive"))
      (node (ref "R19") (pin "2") (pinfunction "2_2") (pintype "passive"))
    )
    (net (code "46") (name "Net-(Q3-C)") (class "Default")
      (node (ref "Q3") (pin "2") (pinfunction "C_2") (pintype "passive"))
      (node (ref "R14") (pin "2") (pinfunction "2_2") (pintype "passive"))
    )
    (net (code "47") (name "Net-(R12-Pad1)") (class "Default")
      (node (ref "R12") (pin "1") (pinfunction "1_1") (pintype "passive"))
      (node (ref "R8") (pin "1") (pinfunction "1_1") (pintype "passive"))
      (node (ref "S1") (pin "1") (pinfunction "1_1") (pintype "passive"))
    )
    (net (code "48") (name "Net-(U1-SW)") (class "Default")
      (node (ref "L1") (pin "1") (pinfunction "1_1") (pintype "passive"))
      (node (ref "U1") (pin "5") (pinfunction "SW_5") (pintype "passive"))
    )
    (net (code "49") (name "Net-(U2-TXD)") (class "Default")
      (node (ref "R5") (pin "2") (pinfunction "2_2") (pintype "passive"))
      (node (ref "U2") (pin "6") (pinfunction "TXD_6") (pintype "passive"))
    )
    (net (code "50") (name "Net-(U2-V3)") (class "Default")
      (node (ref "C8") (pin "1") (pinfunction "1_1") (pintype "passive"))
      (node (ref "U2") (pin "8") (pinfunction "V3_8") (pintype "passive"))
    )
    (net (code "51") (name "Net-(U3-PROG)") (class "Default")
      (node (ref "R31") (pin "1") (pinfunction "1_1") (pintype "passive"))
      (node (ref "U3") (pin "2") (pinfunction "PROG_2") (pintype "bidirectional"))
    )
    (net (code "52") (name "VBUS") (class "Default")
      (node (ref "J1") (pin "A4_B9") (pinfunction "VBUS_A4_B9") (pintype "power_in"))
      (node (ref "J1") (pin "B4_A9") (pinfunction "VBUS_B4_A9") (pintype "power_in"))
      (node (ref "R26") (pin "1") (pinfunction "1_1") (pintype "passive"))
    )
    (net (code "53") (name "VBUS_IN") (class "Default")
      (node (ref "C14") (pin "2") (pinfunction "2_2") (pintype "passive"))
      (node (ref "R26") (pin "2") (pinfunction "2_2") (pintype "passive"))
      (node (ref "R28") (pin "1") (pinfunction "1_1") (pintype "passive"))
      (node (ref "R29") (pin "1") (pinfunction "1_1") (pintype "passive"))
      (node (ref "U3") (pin "4") (pinfunction "VCC_4") (pintype "power_in"))
      (node (ref "U3") (pin "8") (pinfunction "CE_8") (pintype "input"))
    )
    (net (code "54") (name "VOUT") (class "Default")
      (node (ref "C1") (pin "2") (pinfunction "2_2") (pintype "passive"))
      (node (ref "L1") (pin "2") (pinfunction "2_2") (pintype "passive"))
      (node (ref "Q2") (pin "6") (pinfunction "D@4_6") (pintype "passive"))
      (node (ref "U1") (pin "1") (pinfunction "EN_1") (pintype "passive"))
      (node (ref "U1") (pin "8") (pinfunction "VIN_8") (pintype "passive"))
    )
    (net (code "55") (name "unconnected-(IC1-3V3-Pad6)") (class "Default")
      (node (ref "IC1") (pin "6") (pinfunction "3V3_6") (pintype "passive+no_connect"))
    )
    (net (code "56") (name "unconnected-(IC1-DM-Pad4)") (class "Default")
      (node (ref "IC1") (pin "4") (pinfunction "DM_4") (pintype "passive+no_connect"))
    )
    (net (code "57") (name "unconnected-(IC1-DP-Pad5)") (class "Default")
      (node (ref "IC1") (pin "5") (pinfunction "DP_5") (pintype "passive+no_connect"))
    )
    (net (code "58") (name "unconnected-(IC1-PA3-Pad1)") (class "Default")
      (node (ref "IC1") (pin "1") (pinfunction "PA3_1") (pintype "passive+no_connect"))
    )
    (net (code "59") (name "unconnected-(IC1-PA4-Pad2)") (class "Default")
      (node (ref "IC1") (pin "2") (pinfunction "PA4_2") (pintype "passive+no_connect"))
    )
    (net (code "60") (name "unconnected-(IC1-PA5-Pad3)") (class "Default")
      (node (ref "IC1") (pin "3") (pinfunction "PA5_3") (pintype "passive+no_connect"))
    )
    (net (code "61") (name "unconnected-(IC1-PB2-Pad24)") (class "Default")
      (node (ref "IC1") (pin "24") (pinfunction "PB2_24") (pintype "passive+no_connect"))
    )
    (net (code "62") (name "unconnected-(IC1-PB4-Pad22)") (class "Default")
      (node (ref "IC1") (pin "22") (pinfunction "PB4_22") (pintype "passive+no_connect"))
    )
    (net (code "63") (name "unconnected-(IC1-PB5-Pad21)") (class "Default")
      (node (ref "IC1") (pin "21") (pinfunction "PB5_21") (pintype "passive+no_connect"))
    )
    (net (code "64") (name "unconnected-(IC1-PB6-Pad20)") (class "Default")
      (node (ref "IC1") (pin "20") (pinfunction "PB6_20") (pintype "passive+no_connect"))
    )
    (net (code "65") (name "unconnected-(IC1-PC1-Pad14)") (class "Default")
      (node (ref "IC1") (pin "14") (pinfunction "PC1_14") (pintype "passive"))
    )
    (net (code "66") (name "unconnected-(IC1-PC3-Pad15)") (class "Default")
      (node (ref "IC1") (pin "15") (pinfunction "PC3_15") (pintype "passive+no_connect"))
    )
    (net (code "67") (name "unconnected-(IC1-PC4-Pad16)") (class "Default")
      (node (ref "IC1") (pin "16") (pinfunction "PC4_16") (pintype "passive+no_connect"))
    )
    (net (code "68") (name "unconnected-(IC1-PC5-Pad17)") (class "Default")
      (node (ref "IC1") (pin "17") (pinfunction "PC5_17") (pintype "passive+no_connect"))
    )
    (net (code "69") (name "unconnected-(IC1-PR1-Pad19)") (class "Default")
      (node (ref "IC1") (pin "19") (pinfunction "PR1_19") (pintype "passive+no_connect"))
    )
    (net (code "70") (name "unconnected-(IC1-PR2-Pad18)") (class "Default")
      (node (ref "IC1") (pin "18") (pinfunction "PR2_18") (pintype "passive+no_connect"))
    )
    (net (code "71") (name "unconnected-(IC2-EXTCLK_{slash}PA3-Pad2)") (class "Default")
      (node (ref "IC2") (pin "2") (pinfunction "EXTCLK_/PA3_2") (pintype "passive+no_connect"))
    )
    (net (code "72") (name "unconnected-(IC2-PA1-Pad24)") (class "Default")
      (node (ref "IC2") (pin "24") (pinfunction "PA1_24") (pintype "passive+no_connect"))
    )
    (net (code "73") (name "unconnected-(IC2-PA4-Pad5)") (class "Default")
      (node (ref "IC2") (pin "5") (pinfunction "PA4_5") (pintype "passive+no_connect"))
    )
    (net (code "74") (name "unconnected-(IC2-PA7-Pad8)") (class "Default")
      (node (ref "IC2") (pin "8") (pinfunction "PA7_8") (pintype "passive+no_connect"))
    )
    (net (code "75") (name "unconnected-(IC2-PB1-Pad15)") (class "Default")
      (node (ref "IC2") (pin "15") (pinfunction "PB1_15") (pintype "passive+no_connect"))
    )
    (net (code "76") (name "unconnected-(IC2-PB4-Pad12)") (class "Default")
      (node (ref "IC2") (pin "12") (pinfunction "PB4_12") (pintype "passive+no_connect"))
    )
    (net (code "77") (name "unconnected-(IC2-PB7-Pad9)") (class "Default")
      (node (ref "IC2") (pin "9") (pinfunction "PB7_9") (pintype "passive+no_connect"))
    )
    (net (code "78") (name "unconnected-(IC2-PC3-Pad20)") (class "Default")
      (node (ref "IC2") (pin "20") (pinfunction "PC3_20") (pintype "passive+no_connect"))
    )
    (net (code "79") (name "unconnected-(IC2-PC4-Pad21)") (class "Default")
      (node (ref "IC2") (pin "21") (pinfunction "PC4_21") (pintype "passive+no_connect"))
    )
    (net (code "80") (name "unconnected-(IC2-PC5-Pad22)") (class "Default")
      (node (ref "IC2") (pin "22") (pinfunction "PC5_22") (pintype "passive+no_connect"))
    )
    (net (code "81") (name "unconnected-(J1-CC2-PadB5)") (class "Default")
      (node (ref "J1") (pin "B5") (pinfunction "CC2_B5") (pintype "bidirectional+no_connect"))
    )
    (net (code "82") (name "unconnected-(J1-DN1-PadA7)") (class "Default")
      (node (ref "J1") (pin "A7") (pinfunction "DN1_A7") (pintype "bidirectional+no_connect"))
    )
    (net (code "83") (name "unconnected-(J1-DP1-PadA6)") (class "Default")
      (node (ref "J1") (pin "A6") (pinfunction "DP1_A6") (pintype "bidirectional+no_connect"))
    )
    (net (code "84") (name "unconnected-(J1-SBU1-PadA8)") (class "Default")
      (node (ref "J1") (pin "A8") (pinfunction "SBU1_A8") (pintype "bidirectional+no_connect"))
    )
    (net (code "85") (name "unconnected-(J1-SBU2-PadB8)") (class "Default")
      (node (ref "J1") (pin "B8") (pinfunction "SBU2_B8") (pintype "bidirectional+no_connect"))
    )
    (net (code "86") (name "unconnected-(Q2-D@1-Pad1)") (class "Default")
      (node (ref "Q2") (pin "1") (pinfunction "D@1_1") (pintype "passive"))
    )
    (net (code "87") (name "unconnected-(Q2-D@2-Pad2)") (class "Default")
      (node (ref "Q2") (pin "2") (pinfunction "D@2_2") (pintype "passive"))
    )
    (net (code "88") (name "unconnected-(Q2-D@3-Pad5)") (class "Default")
      (node (ref "Q2") (pin "5") (pinfunction "D@3_5") (pintype "passive"))
    )
    (net (code "89") (name "unconnected-(U1-NC-Pad2)") (class "Default")
      (node (ref "U1") (pin "2") (pinfunction "NC_2") (pintype "passive+no_connect"))
    )
    (net (code "90") (name "unconnected-(U1-PG-Pad3)") (class "Default")
      (node (ref "U1") (pin "3") (pinfunction "PG_3") (pintype "passive+no_connect"))
    )
    (net (code "91") (name "unconnected-(U2-RTS#-Pad4)") (class "Default")
      (node (ref "U2") (pin "4") (pinfunction "RTS#_4") (pintype "passive+no_connect"))
    )
  )
)
